# Bumblebee.net
KiCad netlist of a schematic drawn in Altium Designer
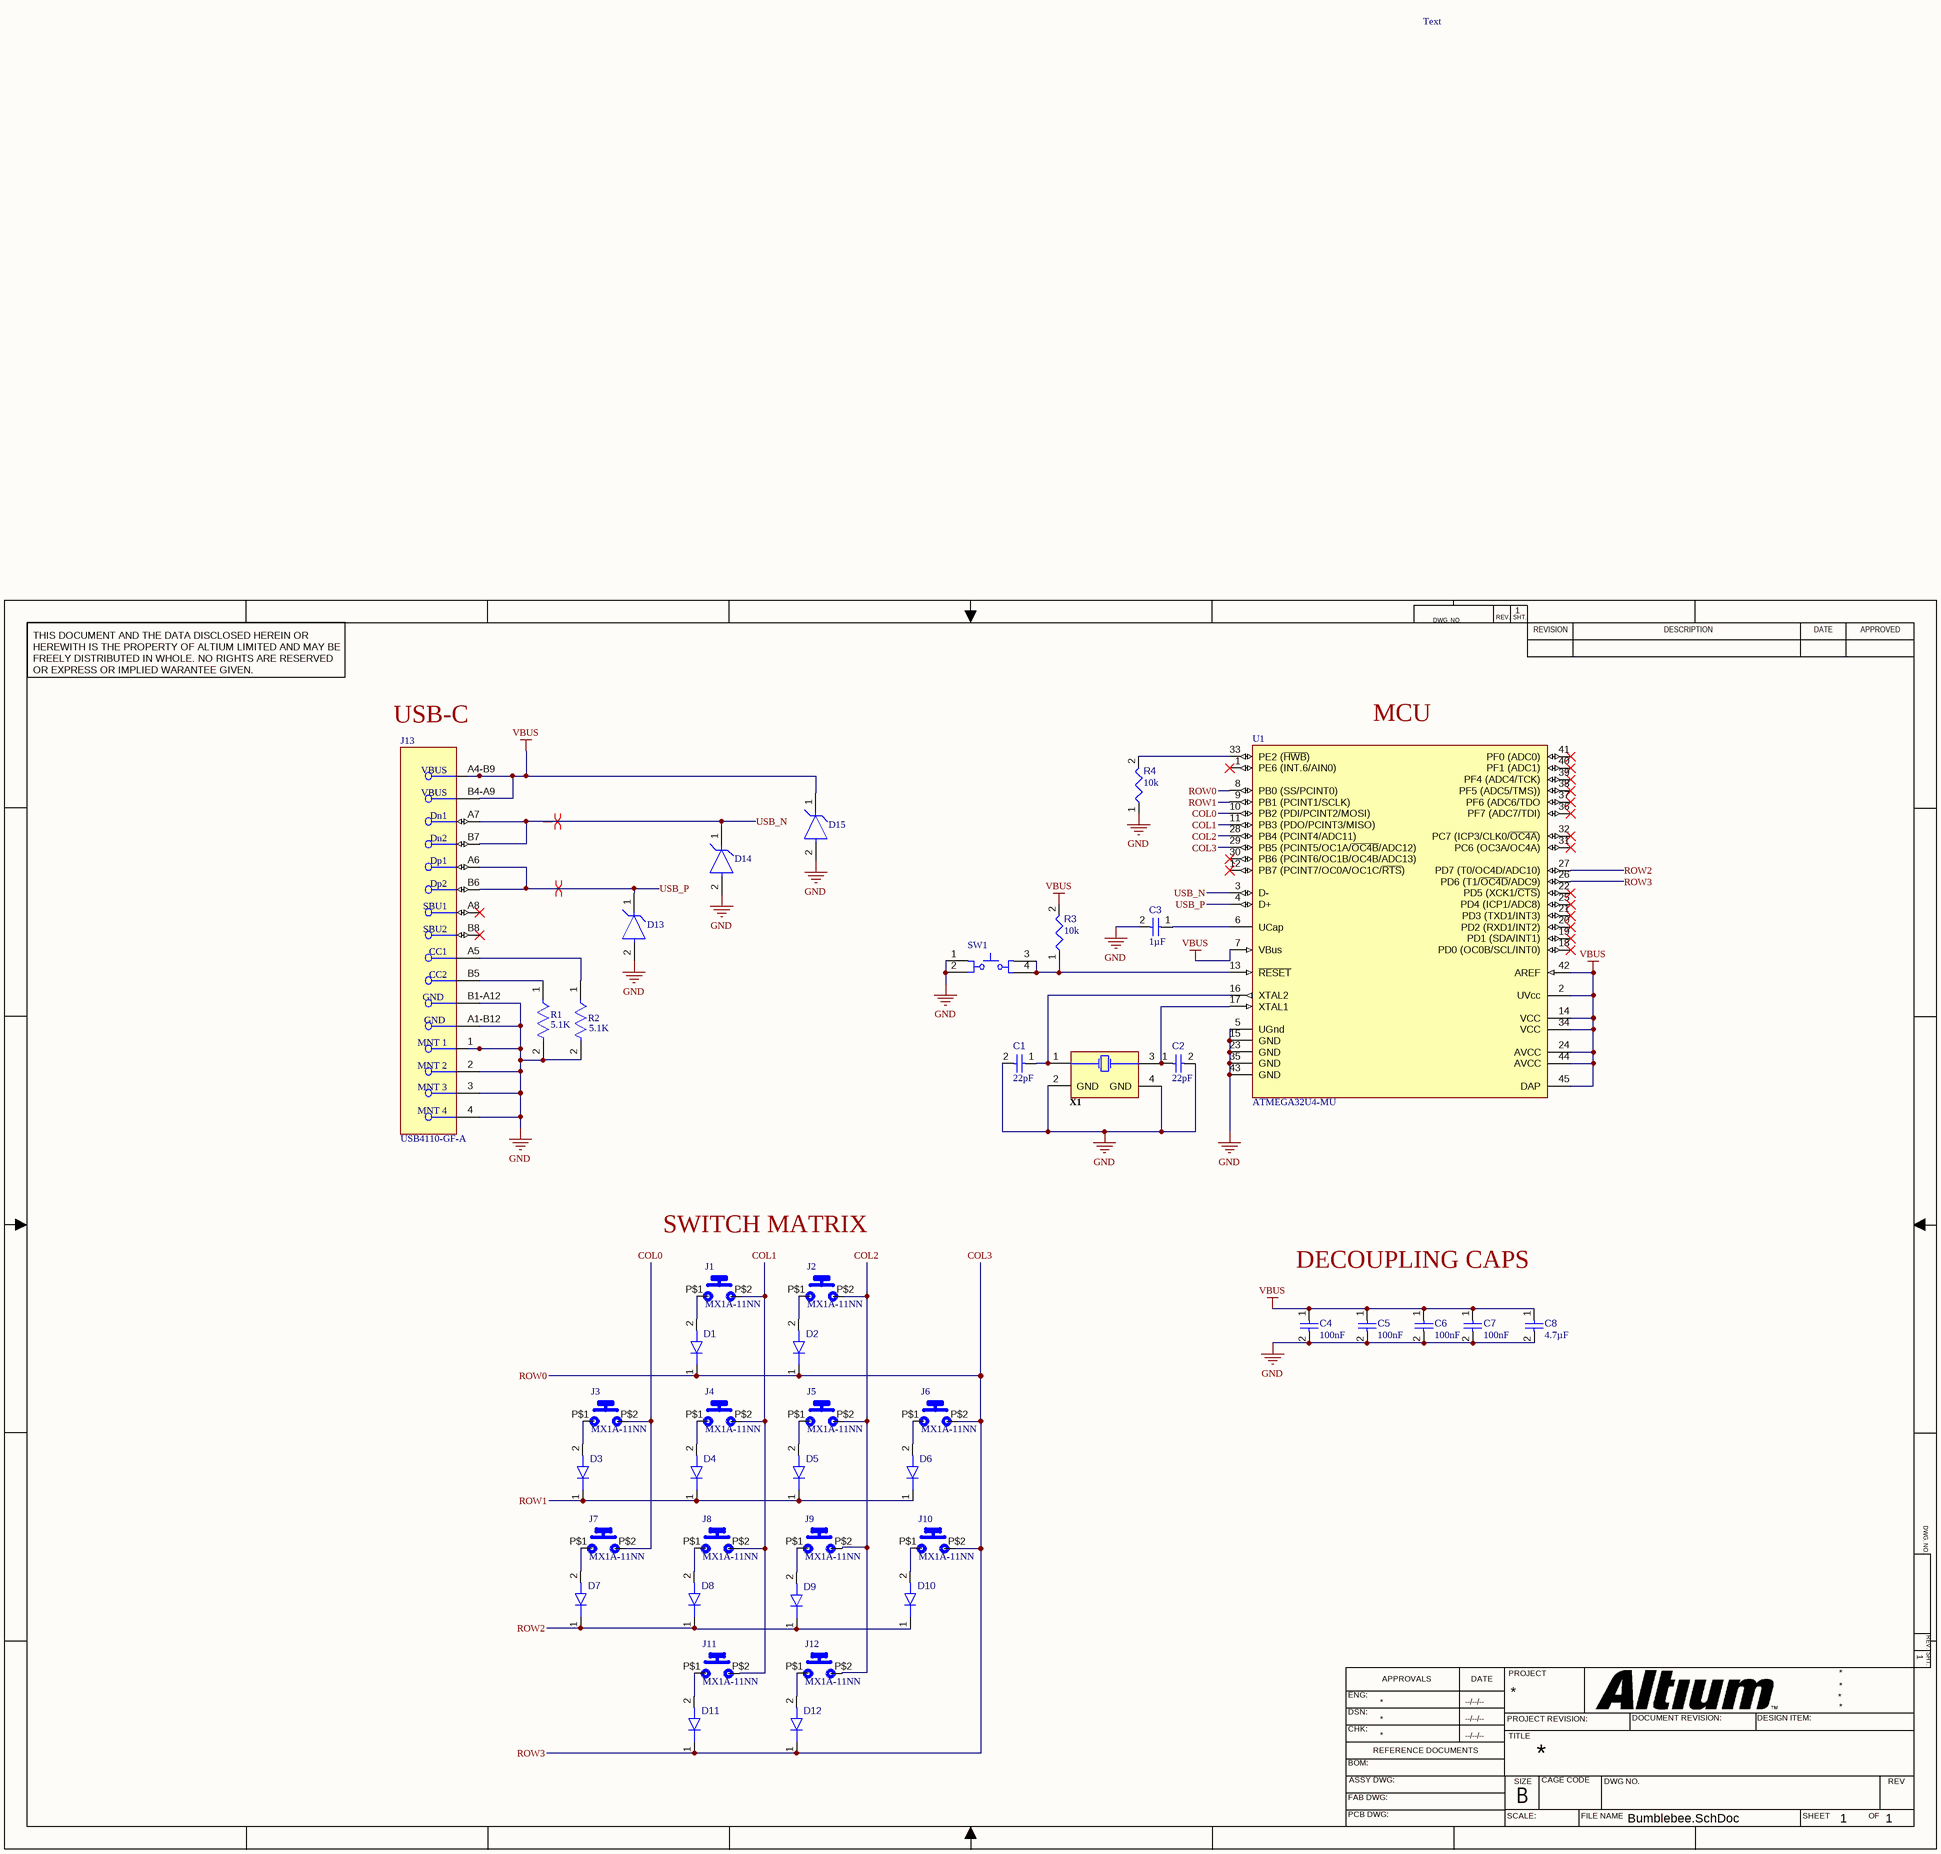
[diagram p0: Bumblebee.SchDoc]

(export (version "E")
  (design (tool "Eeschema 10.0.6"))
  (components
    (comp (ref "C1")
      (value "22pF")
      (footprint "CAPC0402(1005)60_L")
      (description "Chip Capacitor, 22pF +/-10%, 50V, 0402, Thickness 0.6 mm")
      (fields (field (name "TOLERANCE") "10%") (field (name "Comment") "Capacitor 22pF +/-10% 50V 0402"))
      (libsource (lib "University of South Florida") (part "CAP-NP-2"))
    )
    (comp (ref "C2")
      (value "22pF")
      (footprint "CAPC0402(1005)60_L")
      (description "Chip Capacitor, 22pF +/-10%, 50V, 0402, Thickness 0.6 mm")
      (fields (field (name "TOLERANCE") "10%") (field (name "Comment") "Capacitor 22pF +/-10% 50V 0402"))
      (libsource (lib "University of South Florida") (part "CAP-NP-2"))
    )
    (comp (ref "C3")
      (value "1µF")
      (footprint "CAPC1005X55X25LL05T10")
      (description "Chip Capacitor, 1 uF, +/- 10%, 6.3 V, 0402 (1005 Metric)")
      (fields (field (name "TOLERANCE") "10%") (field (name "Comment") "Capacitor 1 uF +/- 10% 6.3 V 0402"))
      (libsource (lib "University of South Florida") (part "CAP-NP-2"))
    )
    (comp (ref "C4")
      (value "100nF")
      (footprint "CAPC1005X56X25LL10T15")
      (description "Chip Capacitor, 0.1 uF, +/- 5%, 16 V, 0402 (1005 Metric)")
      (fields (field (name "TOLERANCE") "5%") (field (name "Comment") "Capacitor 0.1 uF +/- 5% 16 V 0402"))
      (libsource (lib "University of South Florida") (part "CAP-NP-2"))
    )
    (comp (ref "C5")
      (value "100nF")
      (footprint "CAPC1005X56X25LL10T15")
      (description "Chip Capacitor, 0.1 uF, +/- 5%, 16 V, 0402 (1005 Metric)")
      (fields (field (name "TOLERANCE") "5%") (field (name "Comment") "Capacitor 0.1 uF +/- 5% 16 V 0402"))
      (libsource (lib "University of South Florida") (part "CAP-NP-2"))
    )
    (comp (ref "C6")
      (value "100nF")
      (footprint "CAPC1005X56X25LL10T15")
      (description "Chip Capacitor, 0.1 uF, +/- 5%, 16 V, 0402 (1005 Metric)")
      (fields (field (name "TOLERANCE") "5%") (field (name "Comment") "Capacitor 0.1 uF +/- 5% 16 V 0402"))
      (libsource (lib "University of South Florida") (part "CAP-NP-2"))
    )
    (comp (ref "C7")
      (value "100nF")
      (footprint "CAPC1005X56X25LL10T15")
      (description "Chip Capacitor, 0.1 uF, +/- 5%, 16 V, 0402 (1005 Metric)")
      (fields (field (name "TOLERANCE") "5%") (field (name "Comment") "Capacitor 0.1 uF +/- 5% 16 V 0402"))
      (libsource (lib "University of South Florida") (part "CAP-NP-2"))
    )
    (comp (ref "C8")
      (value "4.7µF")
      (footprint "CAPC0603(1608)100_L")
      (description "Chip Capacitor, 4.7µF +/-20%, 10V, 0603, Thickness 1 mm")
      (fields (field (name "TOLERANCE") "10%") (field (name "Comment") "Capacitor 4.7µF +/-20% 10V 0603"))
      (libsource (lib "University of South Florida") (part "CAP-NP-2"))
    )
    (comp (ref "D1")
      (value "1SS400CSFH")
      (footprint "ROHM-VMN2-2_V")
      (description "Switching Diode (High Speed Switching), 80 V, 100 mA, 2-Pin SOD-923, RoHS, Tape and Reel")
      (libsource (lib "University of South Florida") (part "D-KA-2"))
    )
    (comp (ref "D2")
      (value "1SS400CSFH")
      (footprint "ROHM-VMN2-2_V")
      (description "Switching Diode (High Speed Switching), 80 V, 100 mA, 2-Pin SOD-923, RoHS, Tape and Reel")
      (libsource (lib "University of South Florida") (part "D-KA-2"))
    )
    (comp (ref "D3")
      (value "1SS400CSFH")
      (footprint "ROHM-VMN2-2_V")
      (description "Switching Diode (High Speed Switching), 80 V, 100 mA, 2-Pin SOD-923, RoHS, Tape and Reel")
      (libsource (lib "University of South Florida") (part "D-KA-2"))
    )
    (comp (ref "D4")
      (value "1SS400CSFH")
      (footprint "ROHM-VMN2-2_V")
      (description "Switching Diode (High Speed Switching), 80 V, 100 mA, 2-Pin SOD-923, RoHS, Tape and Reel")
      (libsource (lib "University of South Florida") (part "D-KA-2"))
    )
    (comp (ref "D5")
      (value "1SS400CSFH")
      (footprint "ROHM-VMN2-2_V")
      (description "Switching Diode (High Speed Switching), 80 V, 100 mA, 2-Pin SOD-923, RoHS, Tape and Reel")
      (libsource (lib "University of South Florida") (part "D-KA-2"))
    )
    (comp (ref "D6")
      (value "1SS400CSFH")
      (footprint "ROHM-VMN2-2_V")
      (description "Switching Diode (High Speed Switching), 80 V, 100 mA, 2-Pin SOD-923, RoHS, Tape and Reel")
      (libsource (lib "University of South Florida") (part "D-KA-2"))
    )
    (comp (ref "D7")
      (value "1SS400CSFH")
      (footprint "ROHM-VMN2-2_V")
      (description "Switching Diode (High Speed Switching), 80 V, 100 mA, 2-Pin SOD-923, RoHS, Tape and Reel")
      (libsource (lib "University of South Florida") (part "D-KA-2"))
    )
    (comp (ref "D8")
      (value "1SS400CSFH")
      (footprint "ROHM-VMN2-2_V")
      (description "Switching Diode (High Speed Switching), 80 V, 100 mA, 2-Pin SOD-923, RoHS, Tape and Reel")
      (libsource (lib "University of South Florida") (part "D-KA-2"))
    )
    (comp (ref "D9")
      (value "1SS400CSFH")
      (footprint "ROHM-VMN2-2_V")
      (description "Switching Diode (High Speed Switching), 80 V, 100 mA, 2-Pin SOD-923, RoHS, Tape and Reel")
      (libsource (lib "University of South Florida") (part "D-KA-2"))
    )
    (comp (ref "D10")
      (value "1SS400CSFH")
      (footprint "ROHM-VMN2-2_V")
      (description "Switching Diode (High Speed Switching), 80 V, 100 mA, 2-Pin SOD-923, RoHS, Tape and Reel")
      (libsource (lib "University of South Florida") (part "D-KA-2"))
    )
    (comp (ref "D11")
      (value "1SS400CSFH")
      (footprint "ROHM-VMN2-2_V")
      (description "Switching Diode (High Speed Switching), 80 V, 100 mA, 2-Pin SOD-923, RoHS, Tape and Reel")
      (libsource (lib "University of South Florida") (part "D-KA-2"))
    )
    (comp (ref "D12")
      (value "1SS400CSFH")
      (footprint "ROHM-VMN2-2_V")
      (description "Switching Diode (High Speed Switching), 80 V, 100 mA, 2-Pin SOD-923, RoHS, Tape and Reel")
      (libsource (lib "University of South Florida") (part "D-KA-2"))
    )
    (comp (ref "D13")
      (value "CPDU5V0USP-HF")
      (footprint "FP-0603-SOD-523F-MFG")
      (description "Tvs Diode 5V 25V 0603/SOD523F")
      (libsource (lib "University of South Florida") (part "f813f71cba58e380607f5dd3caf9714"))
    )
    (comp (ref "D14")
      (value "CPDU5V0USP-HF")
      (footprint "FP-0603-SOD-523F-MFG")
      (description "Tvs Diode 5V 25V 0603/SOD523F")
      (libsource (lib "University of South Florida") (part "f813f71cba58e380607f5dd3caf9714"))
    )
    (comp (ref "D15")
      (value "CPDU5V0USP-HF")
      (footprint "FP-0603-SOD-523F-MFG")
      (description "Tvs Diode 5V 25V 0603/SOD523F")
      (libsource (lib "University of South Florida") (part "f813f71cba58e380607f5dd3caf9714"))
    )
    (comp (ref "J1")
      (value "MX1A-11NN")
      (footprint "CHERRY_MX1A-11NN_SWITCH")
      (description "Pushbutton Switch SPST-NO Keyswitch Panel Mount, Front")
      (fields (field (name "MF") "Cherry"))
      (libsource (lib "University of South Florida") (part "MX1A-11NN"))
    )
    (comp (ref "J2")
      (value "MX1A-11NN")
      (footprint "CHERRY_MX1A-11NN_SWITCH")
      (description "Pushbutton Switch SPST-NO Keyswitch Panel Mount, Front")
      (fields (field (name "MF") "Cherry"))
      (libsource (lib "University of South Florida") (part "MX1A-11NN"))
    )
    (comp (ref "J3")
      (value "MX1A-11NN")
      (footprint "CHERRY_MX1A-11NN_SWITCH")
      (description "Pushbutton Switch SPST-NO Keyswitch Panel Mount, Front")
      (fields (field (name "MF") "Cherry"))
      (libsource (lib "University of South Florida") (part "MX1A-11NN"))
    )
    (comp (ref "J4")
      (value "MX1A-11NN")
      (footprint "CHERRY_MX1A-11NN_SWITCH")
      (description "Pushbutton Switch SPST-NO Keyswitch Panel Mount, Front")
      (fields (field (name "MF") "Cherry"))
      (libsource (lib "University of South Florida") (part "MX1A-11NN"))
    )
    (comp (ref "J5")
      (value "MX1A-11NN")
      (footprint "CHERRY_MX1A-11NN_SWITCH")
      (description "Pushbutton Switch SPST-NO Keyswitch Panel Mount, Front")
      (fields (field (name "MF") "Cherry"))
      (libsource (lib "University of South Florida") (part "MX1A-11NN"))
    )
    (comp (ref "J6")
      (value "MX1A-11NN")
      (footprint "CHERRY_MX1A-11NN_SWITCH")
      (description "Pushbutton Switch SPST-NO Keyswitch Panel Mount, Front")
      (fields (field (name "MF") "Cherry"))
      (libsource (lib "University of South Florida") (part "MX1A-11NN"))
    )
    (comp (ref "J7")
      (value "MX1A-11NN")
      (footprint "CHERRY_MX1A-11NN_SWITCH")
      (description "Pushbutton Switch SPST-NO Keyswitch Panel Mount, Front")
      (fields (field (name "MF") "Cherry"))
      (libsource (lib "University of South Florida") (part "MX1A-11NN"))
    )
    (comp (ref "J8")
      (value "MX1A-11NN")
      (footprint "CHERRY_MX1A-11NN_SWITCH")
      (description "Pushbutton Switch SPST-NO Keyswitch Panel Mount, Front")
      (fields (field (name "MF") "Cherry"))
      (libsource (lib "University of South Florida") (part "MX1A-11NN"))
    )
    (comp (ref "J9")
      (value "MX1A-11NN")
      (footprint "CHERRY_MX1A-11NN_SWITCH")
      (description "Pushbutton Switch SPST-NO Keyswitch Panel Mount, Front")
      (fields (field (name "MF") "Cherry"))
      (libsource (lib "University of South Florida") (part "MX1A-11NN"))
    )
    (comp (ref "J10")
      (value "MX1A-11NN")
      (footprint "CHERRY_MX1A-11NN_SWITCH")
      (description "Pushbutton Switch SPST-NO Keyswitch Panel Mount, Front")
      (fields (field (name "MF") "Cherry"))
      (libsource (lib "University of South Florida") (part "MX1A-11NN"))
    )
    (comp (ref "J11")
      (value "MX1A-11NN")
      (footprint "CHERRY_MX1A-11NN_SWITCH")
      (description "Pushbutton Switch SPST-NO Keyswitch Panel Mount, Front")
      (fields (field (name "MF") "Cherry"))
      (libsource (lib "University of South Florida") (part "MX1A-11NN"))
    )
    (comp (ref "J12")
      (value "MX1A-11NN")
      (footprint "CHERRY_MX1A-11NN_SWITCH")
      (description "Pushbutton Switch SPST-NO Keyswitch Panel Mount, Front")
      (fields (field (name "MF") "Cherry"))
      (libsource (lib "University of South Florida") (part "MX1A-11NN"))
    )
    (comp (ref "J13")
      (value "USB4110-GF-A")
      (footprint "FP-USB4110-GF-A-MFG")
      (description "Conn USB Type C RCP 16 POS 0.3mm/0.5mm Solder ST SMD 16 Terminal 1 Port T/R")
      (libsource (lib "University of South Florida") (part "e23f2b38bb3c3f98e683ebab9ede730"))
    )
    (comp (ref "R1")
      (value "5.1K")
      (footprint "FP-ERA3A-MFG")
      (description "Res Thin Film 0603 5.1K Ohm 0.1% 1/10W ±25ppm/°C Molded SMD SMD Punched Carrier T/R")
      (fields (field (name "Comment") "ERA-3AEB512V"))
      (libsource (lib "University of South Florida") (part "8db39607336c341a927600551d01821"))
    )
    (comp (ref "R2")
      (value "5.1K")
      (footprint "FP-ERA3A-MFG")
      (description "Res Thin Film 0603 5.1K Ohm 0.1% 1/10W ±25ppm/°C Molded SMD SMD Punched Carrier T/R")
      (fields (field (name "Comment") "ERA-3AEB512V"))
      (libsource (lib "University of South Florida") (part "8db39607336c341a927600551d01821"))
    )
    (comp (ref "R3")
      (value "10k")
      (footprint "RESC0402(1005)_L")
      (description "10K 0.063W 1% 0402 (1005 Metric)  SMD")
      (fields (field (name "POWER") "63mW") (field (name "TOLERANCE") "1%"))
      (libsource (lib "University of South Florida") (part "10KR2F"))
    )
    (comp (ref "R4")
      (value "10k")
      (footprint "RESC0402(1005)_L")
      (description "10K 0.063W 1% 0402 (1005 Metric)  SMD")
      (fields (field (name "POWER") "63mW") (field (name "TOLERANCE") "1%"))
      (libsource (lib "University of South Florida") (part "10KR2F"))
    )
    (comp (ref "SW1")
      (value "TL3342F160QG")
      (footprint "ESWI-TL3342F160QG_V")
      (description "Tactile Switch, SPST-NO, 50 mA, 12 V, 4-Pin SMD, RoHS, Tape and Reel")
      (fields (field (name "MANUFACTURER") "E-Switch"))
      (libsource (lib "University of South Florida") (part "SW-SPST-NO-4"))
    )
    (comp (ref "U1")
      (value "ATMEGA32U4-MU")
      (footprint "44PW_L")
      (description "8-bit AVR MCU, 32 KB, 2560 Bytes, 16 MHz, 2.7 to 5.5V, VQFN-44, RoHS")
      (libsource (lib "University of South Florida") (part "MC-8B-ATM16U4-SQ45"))
    )
    (comp (ref "X1")
      (value "7B-16.000MAAJ-T")
      (footprint "TXC-7B-4_V")
      (fields (field (name "MANUFACTURER") "TXC") (field (name "TOLERANCE") "30ppm"))
      (libsource (lib "University of South Florida") (part "XTAL-1-3-4"))
    )
  )
  (nets
    (net (code "1") (name "/COL0") (class "Default")
      (node (ref "J3") (pin "P$2") (pinfunction "S_P$2") (pintype "passive"))
      (node (ref "J7") (pin "P$2") (pinfunction "S_P$2") (pintype "passive"))
      (node (ref "U1") (pin "10") (pinfunction "PB2_(PDI/PCINT2/MOSI)_10") (pintype "bidirectional"))
    )
    (net (code "2") (name "/COL1") (class "Default")
      (node (ref "J1") (pin "P$2") (pinfunction "S_P$2") (pintype "passive"))
      (node (ref "J11") (pin "P$2") (pinfunction "S_P$2") (pintype "passive"))
      (node (ref "J4") (pin "P$2") (pinfunction "S_P$2") (pintype "passive"))
      (node (ref "J8") (pin "P$2") (pinfunction "S_P$2") (pintype "passive"))
      (node (ref "U1") (pin "11") (pinfunction "PB3_(PDO/PCINT3/MISO)_11") (pintype "bidirectional"))
    )
    (net (code "3") (name "/COL2") (class "Default")
      (node (ref "J12") (pin "P$2") (pinfunction "S_P$2") (pintype "passive"))
      (node (ref "J2") (pin "P$2") (pinfunction "S_P$2") (pintype "passive"))
      (node (ref "J5") (pin "P$2") (pinfunction "S_P$2") (pintype "passive"))
      (node (ref "J9") (pin "P$2") (pinfunction "S_P$2") (pintype "passive"))
      (node (ref "U1") (pin "28") (pinfunction "PB4_(PCINT4/ADC11)_28") (pintype "bidirectional"))
    )
    (net (code "4") (name "/COL3") (class "Default")
      (node (ref "D1") (pin "1") (pinfunction "K_1") (pintype "passive"))
      (node (ref "D11") (pin "1") (pinfunction "K_1") (pintype "passive"))
      (node (ref "D12") (pin "1") (pinfunction "K_1") (pintype "passive"))
      (node (ref "D2") (pin "1") (pinfunction "K_1") (pintype "passive"))
      (node (ref "J10") (pin "P$2") (pinfunction "S_P$2") (pintype "passive"))
      (node (ref "J6") (pin "P$2") (pinfunction "S_P$2") (pintype "passive"))
      (node (ref "U1") (pin "26") (pinfunction "PD6_(T1/~{OC4D}/ADC9)_26") (pintype "bidirectional"))
      (node (ref "U1") (pin "29") (pinfunction "PB5_(PCINT5/OC1A/~{OC4B}/ADC12)_29") (pintype "bidirectional"))
      (node (ref "U1") (pin "8") (pinfunction "PB0_(SS/PCINT0)_8") (pintype "bidirectional"))
    )
    (net (code "5") (name "/ROW1") (class "Default")
      (node (ref "D3") (pin "1") (pinfunction "K_1") (pintype "passive"))
      (node (ref "D4") (pin "1") (pinfunction "K_1") (pintype "passive"))
      (node (ref "D5") (pin "1") (pinfunction "K_1") (pintype "passive"))
      (node (ref "D6") (pin "1") (pinfunction "K_1") (pintype "passive"))
      (node (ref "U1") (pin "9") (pinfunction "PB1_(PCINT1/SCLK)_9") (pintype "bidirectional"))
    )
    (net (code "6") (name "/ROW2") (class "Default")
      (node (ref "D10") (pin "1") (pinfunction "K_1") (pintype "passive"))
      (node (ref "D7") (pin "1") (pinfunction "K_1") (pintype "passive"))
      (node (ref "D8") (pin "1") (pinfunction "K_1") (pintype "passive"))
      (node (ref "D9") (pin "1") (pinfunction "K_1") (pintype "passive"))
      (node (ref "U1") (pin "27") (pinfunction "PD7_(T0/OC4D/ADC10)_27") (pintype "bidirectional"))
    )
    (net (code "7") (name "/USB_N") (class "Default")
      (node (ref "D14") (pin "1") (pinfunction "C_1") (pintype "passive"))
      (node (ref "J13") (pin "A7") (pinfunction "Dn1_A7") (pintype "bidirectional"))
      (node (ref "J13") (pin "B7") (pinfunction "Dn2_B7") (pintype "bidirectional"))
      (node (ref "U1") (pin "3") (pinfunction "D-_3") (pintype "bidirectional"))
    )
    (net (code "8") (name "/USB_P") (class "Default")
      (node (ref "D13") (pin "1") (pinfunction "C_1") (pintype "passive"))
      (node (ref "J13") (pin "A6") (pinfunction "Dp1_A6") (pintype "bidirectional"))
      (node (ref "J13") (pin "B6") (pinfunction "Dp2_B6") (pintype "bidirectional"))
      (node (ref "U1") (pin "4") (pinfunction "D+_4") (pintype "bidirectional"))
    )
    (net (code "9") (name "GND") (class "Default")
      (node (ref "C1") (pin "2") (pinfunction "2_2") (pintype "passive"))
      (node (ref "C2") (pin "2") (pinfunction "2_2") (pintype "passive"))
      (node (ref "C3") (pin "2") (pinfunction "2_2") (pintype "passive"))
      (node (ref "C4") (pin "2") (pinfunction "2_2") (pintype "passive"))
      (node (ref "C5") (pin "2") (pinfunction "2_2") (pintype "passive"))
      (node (ref "C6") (pin "2") (pinfunction "2_2") (pintype "passive"))
      (node (ref "C7") (pin "2") (pinfunction "2_2") (pintype "passive"))
      (node (ref "C8") (pin "2") (pinfunction "2_2") (pintype "passive"))
      (node (ref "D13") (pin "2") (pinfunction "A_2") (pintype "passive"))
      (node (ref "D14") (pin "2") (pinfunction "A_2") (pintype "passive"))
      (node (ref "D15") (pin "2") (pinfunction "A_2") (pintype "passive"))
      (node (ref "J13") (pin "1") (pinfunction "MNT_1_1") (pintype "passive"))
      (node (ref "J13") (pin "2") (pinfunction "MNT_2_2") (pintype "passive"))
      (node (ref "J13") (pin "3") (pinfunction "MNT_3_3") (pintype "passive"))
      (node (ref "J13") (pin "4") (pinfunction "MNT_4_4") (pintype "passive"))
      (node (ref "J13") (pin "A1-B12") (pinfunction "GND_A1-B12") (pintype "passive"))
      (node (ref "J13") (pin "B1-A12") (pinfunction "GND_B1-A12") (pintype "passive"))
      (node (ref "R1") (pin "2") (pinfunction "2_2") (pintype "passive"))
      (node (ref "R2") (pin "2") (pinfunction "2_2") (pintype "passive"))
      (node (ref "R4") (pin "1") (pinfunction "1_1") (pintype "passive"))
      (node (ref "SW1") (pin "1") (pinfunction "1_1") (pintype "passive"))
      (node (ref "SW1") (pin "2") (pinfunction "2_2") (pintype "passive"))
      (node (ref "U1") (pin "15") (pinfunction "GND_15") (pintype "power_in"))
      (node (ref "U1") (pin "23") (pinfunction "GND_23") (pintype "power_in"))
      (node (ref "U1") (pin "35") (pinfunction "GND_35") (pintype "power_in"))
      (node (ref "U1") (pin "43") (pinfunction "GND_43") (pintype "power_in"))
      (node (ref "U1") (pin "5") (pinfunction "UGnd_5") (pintype "power_in"))
      (node (ref "X1") (pin "2") (pinfunction "GND_2") (pintype "power_in"))
      (node (ref "X1") (pin "4") (pinfunction "GND_4") (pintype "power_in"))
    )
    (net (code "10") (name "Net-(D1-A)") (class "Default")
      (node (ref "D1") (pin "2") (pinfunction "A_2") (pintype "passive"))
      (node (ref "J1") (pin "P$1") (pinfunction "P_P$1") (pintype "passive"))
    )
    (net (code "11") (name "Net-(D2-A)") (class "Default")
      (node (ref "D2") (pin "2") (pinfunction "A_2") (pintype "passive"))
      (node (ref "J2") (pin "P$1") (pinfunction "P_P$1") (pintype "passive"))
    )
    (net (code "12") (name "Net-(D3-A)") (class "Default")
      (node (ref "D3") (pin "2") (pinfunction "A_2") (pintype "passive"))
      (node (ref "J3") (pin "P$1") (pinfunction "P_P$1") (pintype "passive"))
    )
    (net (code "13") (name "Net-(D4-A)") (class "Default")
      (node (ref "D4") (pin "2") (pinfunction "A_2") (pintype "passive"))
      (node (ref "J4") (pin "P$1") (pinfunction "P_P$1") (pintype "passive"))
    )
    (net (code "14") (name "Net-(D5-A)") (class "Default")
      (node (ref "D5") (pin "2") (pinfunction "A_2") (pintype "passive"))
      (node (ref "J5") (pin "P$1") (pinfunction "P_P$1") (pintype "passive"))
    )
    (net (code "15") (name "Net-(D6-A)") (class "Default")
      (node (ref "D6") (pin "2") (pinfunction "A_2") (pintype "passive"))
      (node (ref "J6") (pin "P$1") (pinfunction "P_P$1") (pintype "passive"))
    )
    (net (code "16") (name "Net-(D7-A)") (class "Default")
      (node (ref "D7") (pin "2") (pinfunction "A_2") (pintype "passive"))
      (node (ref "J7") (pin "P$1") (pinfunction "P_P$1") (pintype "passive"))
    )
    (net (code "17") (name "Net-(D8-A)") (class "Default")
      (node (ref "D8") (pin "2") (pinfunction "A_2") (pintype "passive"))
      (node (ref "J8") (pin "P$1") (pinfunction "P_P$1") (pintype "passive"))
    )
    (net (code "18") (name "Net-(D9-A)") (class "Default")
      (node (ref "D9") (pin "2") (pinfunction "A_2") (pintype "passive"))
      (node (ref "J9") (pin "P$1") (pinfunction "P_P$1") (pintype "passive"))
    )
    (net (code "19") (name "Net-(D10-A)") (class "Default")
      (node (ref "D10") (pin "2") (pinfunction "A_2") (pintype "passive"))
      (node (ref "J10") (pin "P$1") (pinfunction "P_P$1") (pintype "passive"))
    )
    (net (code "20") (name "Net-(D11-A)") (class "Default")
      (node (ref "D11") (pin "2") (pinfunction "A_2") (pintype "passive"))
      (node (ref "J11") (pin "P$1") (pinfunction "P_P$1") (pintype "passive"))
    )
    (net (code "21") (name "Net-(D12-A)") (class "Default")
      (node (ref "D12") (pin "2") (pinfunction "A_2") (pintype "passive"))
      (node (ref "J12") (pin "P$1") (pinfunction "P_P$1") (pintype "passive"))
    )
    (net (code "22") (name "Net-(J13-CC1)") (class "Default")
      (node (ref "J13") (pin "A5") (pinfunction "CC1_A5") (pintype "power_in"))
      (node (ref "R2") (pin "1") (pinfunction "1_1") (pintype "passive"))
    )
    (net (code "23") (name "Net-(J13-CC2)") (class "Default")
      (node (ref "J13") (pin "B5") (pinfunction "CC2_B5") (pintype "power_in"))
      (node (ref "R1") (pin "1") (pinfunction "1_1") (pintype "passive"))
    )
    (net (code "24") (name "Net-(U1-PE2_(~{HWB}))") (class "Default")
      (node (ref "R4") (pin "2") (pinfunction "2_2") (pintype "passive"))
      (node (ref "U1") (pin "33") (pinfunction "PE2_(~{HWB})_33") (pintype "bidirectional"))
    )
    (net (code "25") (name "Net-(U1-UCap)") (class "Default")
      (node (ref "C3") (pin "1") (pinfunction "1_1") (pintype "passive"))
      (node (ref "U1") (pin "6") (pinfunction "UCap_6") (pintype "passive"))
    )
    (net (code "26") (name "Net-(U1-XTAL1)") (class "Default")
      (node (ref "C2") (pin "1") (pinfunction "1_1") (pintype "passive"))
      (node (ref "U1") (pin "17") (pinfunction "XTAL1_17") (pintype "input"))
      (node (ref "X1") (pin "3") (pinfunction "X2_3") (pintype "passive"))
    )
    (net (code "27") (name "Net-(U1-XTAL2)") (class "Default")
      (node (ref "C1") (pin "1") (pinfunction "1_1") (pintype "passive"))
      (node (ref "U1") (pin "16") (pinfunction "XTAL2_16") (pintype "output"))
      (node (ref "X1") (pin "1") (pinfunction "X1_1") (pintype "passive"))
    )
    (net (code "28") (name "Net-(U1-~{RESET})") (class "Default")
      (node (ref "R3") (pin "1") (pinfunction "1_1") (pintype "passive"))
      (node (ref "SW1") (pin "3") (pinfunction "3_3") (pintype "passive"))
      (node (ref "SW1") (pin "4") (pinfunction "4_4") (pintype "passive"))
      (node (ref "U1") (pin "13") (pinfunction "~{RESET}_13") (pintype "input"))
    )
    (net (code "29") (name "VBUS") (class "Default")
      (node (ref "C4") (pin "1") (pinfunction "1_1") (pintype "passive"))
      (node (ref "C5") (pin "1") (pinfunction "1_1") (pintype "passive"))
      (node (ref "C6") (pin "1") (pinfunction "1_1") (pintype "passive"))
      (node (ref "C7") (pin "1") (pinfunction "1_1") (pintype "passive"))
      (node (ref "C8") (pin "1") (pinfunction "1_1") (pintype "passive"))
      (node (ref "D15") (pin "1") (pinfunction "C_1") (pintype "passive"))
      (node (ref "J13") (pin "A4-B9") (pinfunction "VBUS_A4-B9") (pintype "power_in"))
      (node (ref "J13") (pin "B4-A9") (pinfunction "VBUS_B4-A9") (pintype "power_in"))
      (node (ref "R3") (pin "2") (pinfunction "2_2") (pintype "passive"))
      (node (ref "U1") (pin "14") (pinfunction "VCC_14") (pintype "power_in"))
      (node (ref "U1") (pin "2") (pinfunction "UVcc_2") (pintype "power_in"))
      (node (ref "U1") (pin "24") (pinfunction "AVCC_24") (pintype "power_in"))
      (node (ref "U1") (pin "34") (pinfunction "VCC_34") (pintype "power_in"))
      (node (ref "U1") (pin "42") (pinfunction "AREF_42") (pintype "input"))
      (node (ref "U1") (pin "44") (pinfunction "AVCC_44") (pintype "power_in"))
      (node (ref "U1") (pin "45") (pinfunction "DAP_45") (pintype "power_in"))
      (node (ref "U1") (pin "7") (pinfunction "VBus_7") (pintype "input"))
    )
    (net (code "30") (name "unconnected-(J13-SBU1-PadA8)") (class "Default")
      (node (ref "J13") (pin "A8") (pinfunction "SBU1_A8") (pintype "bidirectional+no_connect"))
    )
    (net (code "31") (name "unconnected-(J13-SBU2-PadB8)") (class "Default")
      (node (ref "J13") (pin "B8") (pinfunction "SBU2_B8") (pintype "bidirectional+no_connect"))
    )
    (net (code "32") (name "unconnected-(U1-PB6_(PCINT6{slash}OC1B{slash}OC4B{slash}ADC13)-Pad30)") (class "Default")
      (node (ref "U1") (pin "30") (pinfunction "PB6_(PCINT6/OC1B/OC4B/ADC13)_30") (pintype "bidirectional+no_connect"))
    )
    (net (code "33") (name "unconnected-(U1-PB7_(PCINT7{slash}OC0A{slash}OC1C{slash}~{RTS})-Pad12)") (class "Default")
      (node (ref "U1") (pin "12") (pinfunction "PB7_(PCINT7/OC0A/OC1C/~{RTS})_12") (pintype "bidirectional+no_connect"))
    )
    (net (code "34") (name "unconnected-(U1-PC6_(OC3A{slash}OC4A)-Pad31)") (class "Default")
      (node (ref "U1") (pin "31") (pinfunction "PC6_(OC3A/OC4A)_31") (pintype "bidirectional+no_connect"))
    )
    (net (code "35") (name "unconnected-(U1-PC7_(ICP3{slash}CLK0{slash}~{OC4A})-Pad32)") (class "Default")
      (node (ref "U1") (pin "32") (pinfunction "PC7_(ICP3/CLK0/~{OC4A})_32") (pintype "bidirectional+no_connect"))
    )
    (net (code "36") (name "unconnected-(U1-PD0_(OC0B{slash}SCL{slash}INT0)-Pad18)") (class "Default")
      (node (ref "U1") (pin "18") (pinfunction "PD0_(OC0B/SCL/INT0)_18") (pintype "bidirectional+no_connect"))
    )
    (net (code "37") (name "unconnected-(U1-PD1_(SDA{slash}INT1)-Pad19)") (class "Default")
      (node (ref "U1") (pin "19") (pinfunction "PD1_(SDA/INT1)_19") (pintype "bidirectional+no_connect"))
    )
    (net (code "38") (name "unconnected-(U1-PD2_(RXD1{slash}INT2)-Pad20)") (class "Default")
      (node (ref "U1") (pin "20") (pinfunction "PD2_(RXD1/INT2)_20") (pintype "bidirectional+no_connect"))
    )
    (net (code "39") (name "unconnected-(U1-PD3_(TXD1{slash}INT3)-Pad21)") (class "Default")
      (node (ref "U1") (pin "21") (pinfunction "PD3_(TXD1/INT3)_21") (pintype "bidirectional+no_connect"))
    )
    (net (code "40") (name "unconnected-(U1-PD4_(ICP1{slash}ADC8)-Pad25)") (class "Default")
      (node (ref "U1") (pin "25") (pinfunction "PD4_(ICP1/ADC8)_25") (pintype "bidirectional+no_connect"))
    )
    (net (code "41") (name "unconnected-(U1-PD5_(XCK1{slash}~{CTS})-Pad22)") (class "Default")
      (node (ref "U1") (pin "22") (pinfunction "PD5_(XCK1/~{CTS})_22") (pintype "bidirectional+no_connect"))
    )
    (net (code "42") (name "unconnected-(U1-PE6_(INT.6{slash}AIN0)-Pad1)") (class "Default")
      (node (ref "U1") (pin "1") (pinfunction "PE6_(INT.6/AIN0)_1") (pintype "bidirectional+no_connect"))
    )
    (net (code "43") (name "unconnected-(U1-PF0_(ADC0)-Pad41)") (class "Default")
      (node (ref "U1") (pin "41") (pinfunction "PF0_(ADC0)_41") (pintype "bidirectional+no_connect"))
    )
    (net (code "44") (name "unconnected-(U1-PF1_(ADC1)-Pad40)") (class "Default")
      (node (ref "U1") (pin "40") (pinfunction "PF1_(ADC1)_40") (pintype "bidirectional+no_connect"))
    )
    (net (code "45") (name "unconnected-(U1-PF4_(ADC4{slash}TCK)-Pad39)") (class "Default")
      (node (ref "U1") (pin "39") (pinfunction "PF4_(ADC4/TCK)_39") (pintype "bidirectional+no_connect"))
    )
    (net (code "46") (name "unconnected-(U1-PF5_(ADC5{slash}TMS))-Pad38)") (class "Default")
      (node (ref "U1") (pin "38") (pinfunction "PF5_(ADC5/TMS))_38") (pintype "bidirectional+no_connect"))
    )
    (net (code "47") (name "unconnected-(U1-PF6_(ADC6{slash}TDO-Pad37)") (class "Default")
      (node (ref "U1") (pin "37") (pinfunction "PF6_(ADC6/TDO_37") (pintype "bidirectional+no_connect"))
    )
    (net (code "48") (name "unconnected-(U1-PF7_(ADC7{slash}TDI)-Pad36)") (class "Default")
      (node (ref "U1") (pin "36") (pinfunction "PF7_(ADC7/TDI)_36") (pintype "bidirectional+no_connect"))
    )
  )
)
